# Connector_26P.net
KiCad netlist of a schematic drawn in Altium Designer
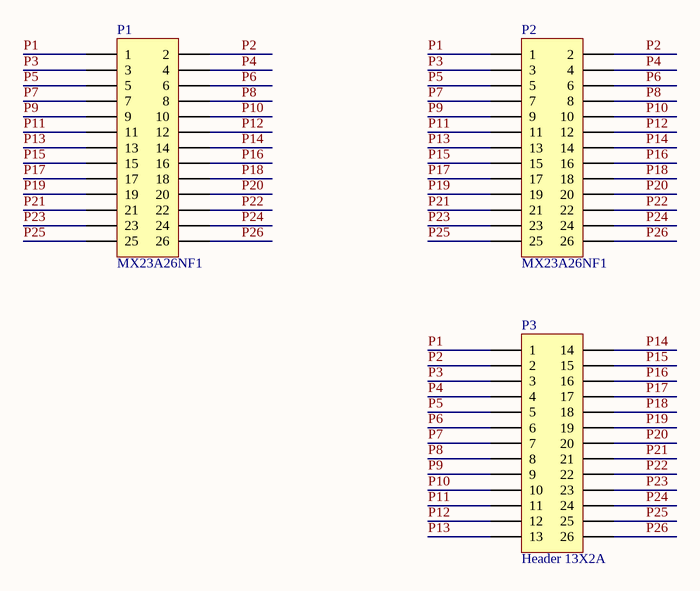
[diagram p0: Connector_26P.SchDoc]

(export (version "E")
  (design (tool "Eeschema 10.0.6"))
  (components
    (comp (ref "P1")
      (value "MX23A26NF1")
      (footprint "MX23A26NF1")
      (description "Header, 13-Pin, Dual row")
      (fields (field (name "PUBLISHER") "Altium Limited"))
      (libsource (lib "Miscellaneous Connectors") (part "MHDR2X13"))
    )
    (comp (ref "P2")
      (value "MX23A26NF1")
      (footprint "MX23A26NF1")
      (description "Header, 13-Pin, Dual row")
      (fields (field (name "PUBLISHER") "Altium Limited"))
      (libsource (lib "Miscellaneous Connectors") (part "MHDR2X13"))
    )
    (comp (ref "P3")
      (value "Header 13X2A")
      (footprint "HDR2X13_CEN")
      (description "Header, 13-Pin, Dual row")
      (fields (field (name "PUBLISHER") "Altium Limited"))
      (libsource (lib "Miscellaneous Connectors") (part "Header 13X2A"))
    )
  )
  (nets
    (net (code "1") (name "/P1") (class "Default")
      (node (ref "P1") (pin "1") (pinfunction "1_1") (pintype "passive"))
      (node (ref "P2") (pin "1") (pinfunction "1_1") (pintype "passive"))
      (node (ref "P3") (pin "1") (pinfunction "1_1") (pintype "passive"))
    )
    (net (code "2") (name "/P2") (class "Default")
      (node (ref "P1") (pin "2") (pinfunction "2_2") (pintype "passive"))
      (node (ref "P2") (pin "2") (pinfunction "2_2") (pintype "passive"))
      (node (ref "P3") (pin "2") (pinfunction "2_2") (pintype "passive"))
    )
    (net (code "3") (name "/P3") (class "Default")
      (node (ref "P1") (pin "3") (pinfunction "3_3") (pintype "passive"))
      (node (ref "P2") (pin "3") (pinfunction "3_3") (pintype "passive"))
      (node (ref "P3") (pin "3") (pinfunction "3_3") (pintype "passive"))
    )
    (net (code "4") (name "/P4") (class "Default")
      (node (ref "P1") (pin "4") (pinfunction "4_4") (pintype "passive"))
      (node (ref "P2") (pin "4") (pinfunction "4_4") (pintype "passive"))
      (node (ref "P3") (pin "4") (pinfunction "4_4") (pintype "passive"))
    )
    (net (code "5") (name "/P5") (class "Default")
      (node (ref "P1") (pin "5") (pinfunction "5_5") (pintype "passive"))
      (node (ref "P2") (pin "5") (pinfunction "5_5") (pintype "passive"))
      (node (ref "P3") (pin "5") (pinfunction "5_5") (pintype "passive"))
    )
    (net (code "6") (name "/P6") (class "Default")
      (node (ref "P1") (pin "6") (pinfunction "6_6") (pintype "passive"))
      (node (ref "P2") (pin "6") (pinfunction "6_6") (pintype "passive"))
      (node (ref "P3") (pin "6") (pinfunction "6_6") (pintype "passive"))
    )
    (net (code "7") (name "/P7") (class "Default")
      (node (ref "P1") (pin "7") (pinfunction "7_7") (pintype "passive"))
      (node (ref "P2") (pin "7") (pinfunction "7_7") (pintype "passive"))
      (node (ref "P3") (pin "7") (pinfunction "7_7") (pintype "passive"))
    )
    (net (code "8") (name "/P8") (class "Default")
      (node (ref "P1") (pin "8") (pinfunction "8_8") (pintype "passive"))
      (node (ref "P2") (pin "8") (pinfunction "8_8") (pintype "passive"))
      (node (ref "P3") (pin "8") (pinfunction "8_8") (pintype "passive"))
    )
    (net (code "9") (name "/P9") (class "Default")
      (node (ref "P1") (pin "9") (pinfunction "9_9") (pintype "passive"))
      (node (ref "P2") (pin "9") (pinfunction "9_9") (pintype "passive"))
      (node (ref "P3") (pin "9") (pinfunction "9_9") (pintype "passive"))
    )
    (net (code "10") (name "/P10") (class "Default")
      (node (ref "P1") (pin "10") (pinfunction "10_10") (pintype "passive"))
      (node (ref "P2") (pin "10") (pinfunction "10_10") (pintype "passive"))
      (node (ref "P3") (pin "10") (pinfunction "10_10") (pintype "passive"))
    )
    (net (code "11") (name "/P11") (class "Default")
      (node (ref "P1") (pin "11") (pinfunction "11_11") (pintype "passive"))
      (node (ref "P2") (pin "11") (pinfunction "11_11") (pintype "passive"))
      (node (ref "P3") (pin "11") (pinfunction "11_11") (pintype "passive"))
    )
    (net (code "12") (name "/P12") (class "Default")
      (node (ref "P1") (pin "12") (pinfunction "12_12") (pintype "passive"))
      (node (ref "P2") (pin "12") (pinfunction "12_12") (pintype "passive"))
      (node (ref "P3") (pin "12") (pinfunction "12_12") (pintype "passive"))
    )
    (net (code "13") (name "/P13") (class "Default")
      (node (ref "P1") (pin "13") (pinfunction "13_13") (pintype "passive"))
      (node (ref "P2") (pin "13") (pinfunction "13_13") (pintype "passive"))
      (node (ref "P3") (pin "13") (pinfunction "13_13") (pintype "passive"))
    )
    (net (code "14") (name "/P14") (class "Default")
      (node (ref "P1") (pin "14") (pinfunction "14_14") (pintype "passive"))
      (node (ref "P2") (pin "14") (pinfunction "14_14") (pintype "passive"))
      (node (ref "P3") (pin "14") (pinfunction "14_14") (pintype "passive"))
    )
    (net (code "15") (name "/P15") (class "Default")
      (node (ref "P1") (pin "15") (pinfunction "15_15") (pintype "passive"))
      (node (ref "P2") (pin "15") (pinfunction "15_15") (pintype "passive"))
      (node (ref "P3") (pin "15") (pinfunction "15_15") (pintype "passive"))
    )
    (net (code "16") (name "/P16") (class "Default")
      (node (ref "P1") (pin "16") (pinfunction "16_16") (pintype "passive"))
      (node (ref "P2") (pin "16") (pinfunction "16_16") (pintype "passive"))
      (node (ref "P3") (pin "16") (pinfunction "16_16") (pintype "passive"))
    )
    (net (code "17") (name "/P17") (class "Default")
      (node (ref "P1") (pin "17") (pinfunction "17_17") (pintype "passive"))
      (node (ref "P2") (pin "17") (pinfunction "17_17") (pintype "passive"))
      (node (ref "P3") (pin "17") (pinfunction "17_17") (pintype "passive"))
    )
    (net (code "18") (name "/P18") (class "Default")
      (node (ref "P1") (pin "18") (pinfunction "18_18") (pintype "passive"))
      (node (ref "P2") (pin "18") (pinfunction "18_18") (pintype "passive"))
      (node (ref "P3") (pin "18") (pinfunction "18_18") (pintype "passive"))
    )
    (net (code "19") (name "/P19") (class "Default")
      (node (ref "P1") (pin "19") (pinfunction "19_19") (pintype "passive"))
      (node (ref "P2") (pin "19") (pinfunction "19_19") (pintype "passive"))
      (node (ref "P3") (pin "19") (pinfunction "19_19") (pintype "passive"))
    )
    (net (code "20") (name "/P20") (class "Default")
      (node (ref "P1") (pin "20") (pinfunction "20_20") (pintype "passive"))
      (node (ref "P2") (pin "20") (pinfunction "20_20") (pintype "passive"))
      (node (ref "P3") (pin "20") (pinfunction "20_20") (pintype "passive"))
    )
    (net (code "21") (name "/P21") (class "Default")
      (node (ref "P1") (pin "21") (pinfunction "21_21") (pintype "passive"))
      (node (ref "P2") (pin "21") (pinfunction "21_21") (pintype "passive"))
      (node (ref "P3") (pin "21") (pinfunction "21_21") (pintype "passive"))
    )
    (net (code "22") (name "/P22") (class "Default")
      (node (ref "P1") (pin "22") (pinfunction "22_22") (pintype "passive"))
      (node (ref "P2") (pin "22") (pinfunction "22_22") (pintype "passive"))
      (node (ref "P3") (pin "22") (pinfunction "22_22") (pintype "passive"))
    )
    (net (code "23") (name "/P23") (class "Default")
      (node (ref "P1") (pin "23") (pinfunction "23_23") (pintype "passive"))
      (node (ref "P2") (pin "23") (pinfunction "23_23") (pintype "passive"))
      (node (ref "P3") (pin "23") (pinfunction "23_23") (pintype "passive"))
    )
    (net (code "24") (name "/P24") (class "Default")
      (node (ref "P1") (pin "24") (pinfunction "24_24") (pintype "passive"))
      (node (ref "P2") (pin "24") (pinfunction "24_24") (pintype "passive"))
      (node (ref "P3") (pin "24") (pinfunction "24_24") (pintype "passive"))
    )
    (net (code "25") (name "/P25") (class "Default")
      (node (ref "P1") (pin "25") (pinfunction "25_25") (pintype "passive"))
      (node (ref "P2") (pin "25") (pinfunction "25_25") (pintype "passive"))
      (node (ref "P3") (pin "25") (pinfunction "25_25") (pintype "passive"))
    )
    (net (code "26") (name "/P26") (class "Default")
      (node (ref "P1") (pin "26") (pinfunction "26_26") (pintype "passive"))
      (node (ref "P2") (pin "26") (pinfunction "26_26") (pintype "passive"))
      (node (ref "P3") (pin "26") (pinfunction "26_26") (pintype "passive"))
    )
  )
)
